# Power_regulator.net
KiCad netlist of a schematic drawn in Altium Designer
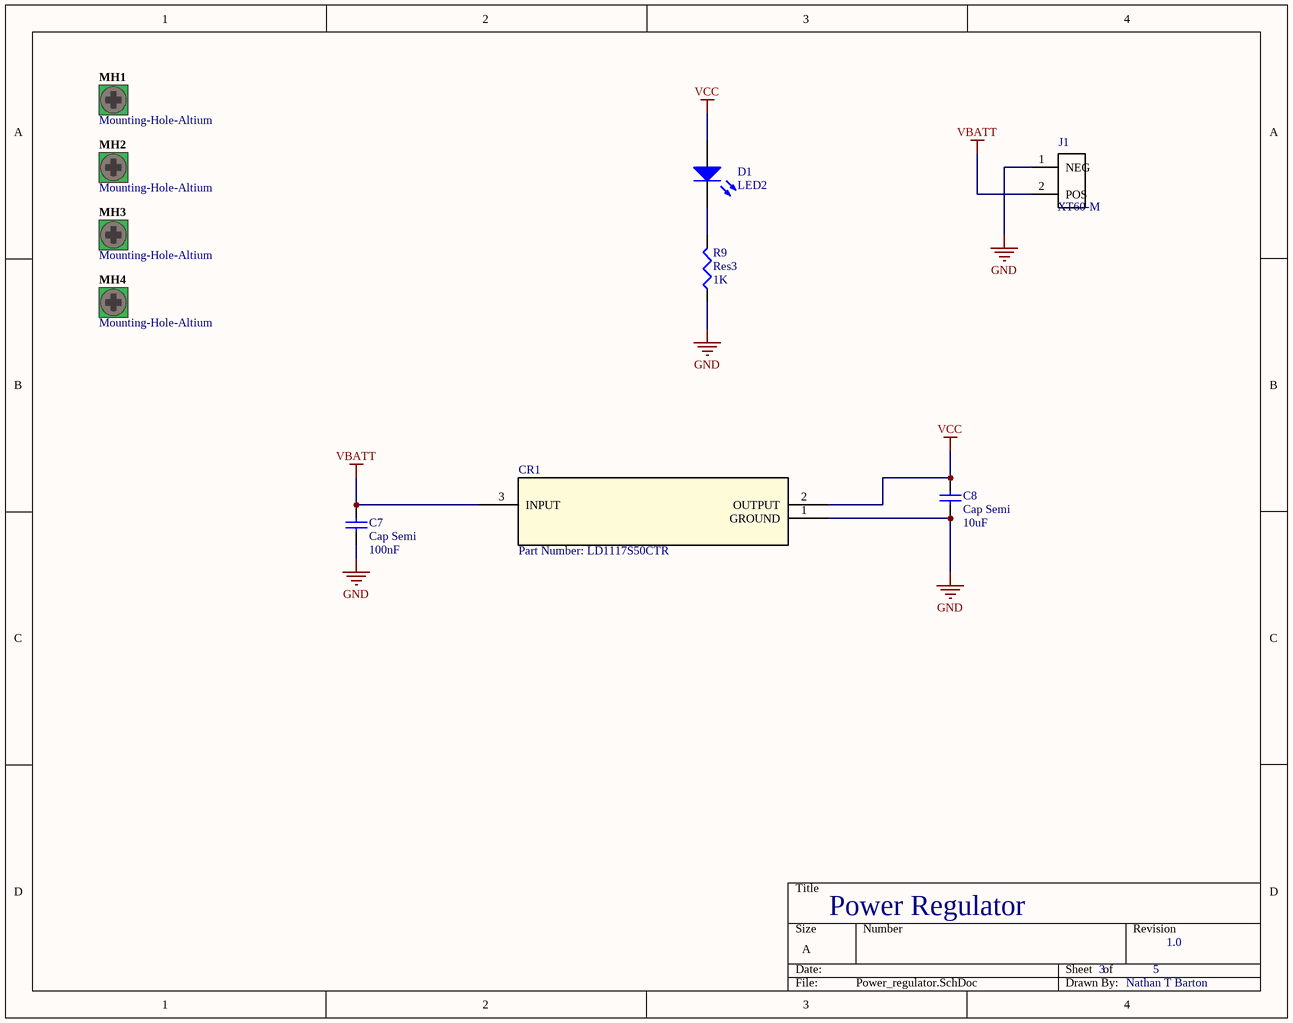
[diagram p0: Power_regulator.SchDoc]

(export (version "E")
  (design (tool "Eeschema 10.0.6"))
  (components
    (comp (ref "C7")
      (value "Cap Semi")
      (footprint "C1206")
      (description "Capacitor (Semiconductor SIM Model)")
      (fields (field (name "ALTIUM_VALUE") "100nF") (field (name "PUBLISHER") "Altium Limited"))
      (libsource (lib "Miscellaneous Devices") (part "Cap Semi"))
    )
    (comp (ref "C8")
      (value "Cap Semi")
      (footprint "C1206")
      (description "Capacitor (Semiconductor SIM Model)")
      (fields (field (name "ALTIUM_VALUE") "10uF") (field (name "PUBLISHER") "Altium Limited"))
      (libsource (lib "Miscellaneous Devices") (part "Cap Semi"))
    )
    (comp (ref "CR1")
      (value "Part Number: LD1117S50CTR")
      (footprint "SOT-223")
      (description "No Description Available")
      (fields
        (field (name "MANUFACTURER_PART_NUMBER") "LD1117S50CTR")
        (field (name "COPYRIGHT") "Copyright (C) 2018 Accelerated Designs. All rights reserved")
      )
      (libsource (lib "spoolbot_library") (part "LD1117S50CTR"))
    )
    (comp (ref "D1")
      (value "LED2")
      (footprint "3.2X1.6X1.1")
      (description "Typical RED, GREEN, YELLOW, AMBER GaAs LED")
      (fields (field (name "PUBLISHER") "Altium Limited"))
      (libsource (lib "Miscellaneous Devices") (part "LED2"))
    )
    (comp (ref "J1")
      (value "XT60-M")
      (footprint "*AMASS_XT60-M")
      (fields (field (name "MF") "AMASS"))
      (libsource (lib "spoolbot_library") (part "XT60-M"))
    )
    (comp (ref "MH1")
      (value "Mounting-Hole-Altium")
      (footprint "Mounting-Hole-Altium")
      (description "Mounting Hole, Altium, 3.8mm pad, 3.4mm plated hole")
      (fields (field (name "PUBLISHER") "Altium"))
      (libsource (lib "Altium Content Vault") (part "Mounting-Hole-Screw"))
    )
    (comp (ref "MH2")
      (value "Mounting-Hole-Altium")
      (footprint "Mounting-Hole-Altium")
      (description "Mounting Hole, Altium, 3.8mm pad, 3.4mm plated hole")
      (fields (field (name "PUBLISHER") "Altium"))
      (libsource (lib "Altium Content Vault") (part "Mounting-Hole-Screw"))
    )
    (comp (ref "MH3")
      (value "Mounting-Hole-Altium")
      (footprint "Mounting-Hole-Altium")
      (description "Mounting Hole, Altium, 3.8mm pad, 3.4mm plated hole")
      (fields (field (name "PUBLISHER") "Altium"))
      (libsource (lib "Altium Content Vault") (part "Mounting-Hole-Screw"))
    )
    (comp (ref "MH4")
      (value "Mounting-Hole-Altium")
      (footprint "Mounting-Hole-Altium")
      (description "Mounting Hole, Altium, 3.8mm pad, 3.4mm plated hole")
      (fields (field (name "PUBLISHER") "Altium"))
      (libsource (lib "Altium Content Vault") (part "Mounting-Hole-Screw"))
    )
    (comp (ref "R9")
      (value "Res3")
      (footprint "J1-0603")
      (description "Resistor")
      (fields (field (name "ALTIUM_VALUE") "1K") (field (name "PUBLISHER") "Altium Limited"))
      (libsource (lib "Miscellaneous Devices") (part "Res3"))
    )
  )
  (nets
    (net (code "1") (name "GND") (class "Default")
      (node (ref "C7") (pin "1") (pinfunction "1_1") (pintype "passive"))
      (node (ref "C8") (pin "1") (pinfunction "1_1") (pintype "passive"))
      (node (ref "CR1") (pin "1") (pinfunction "GROUND_1") (pintype "passive"))
      (node (ref "J1") (pin "1") (pinfunction "NEG_1") (pintype "passive"))
      (node (ref "R9") (pin "1") (pinfunction "1_1") (pintype "passive"))
    )
    (net (code "2") (name "Net-(D1-K)") (class "Default")
      (node (ref "D1") (pin "2") (pinfunction "K_2") (pintype "passive"))
      (node (ref "R9") (pin "2") (pinfunction "2_2") (pintype "passive"))
    )
    (net (code "3") (name "VBATT") (class "Default")
      (node (ref "C7") (pin "2") (pinfunction "2_2") (pintype "passive"))
      (node (ref "CR1") (pin "3") (pinfunction "INPUT_3") (pintype "passive"))
      (node (ref "J1") (pin "2") (pinfunction "POS_2") (pintype "passive"))
    )
    (net (code "4") (name "VCC") (class "Default")
      (node (ref "C8") (pin "2") (pinfunction "2_2") (pintype "passive"))
      (node (ref "CR1") (pin "2") (pinfunction "OUTPUT_2") (pintype "passive"))
      (node (ref "D1") (pin "1") (pinfunction "A_1") (pintype "passive"))
    )
    (net (code "5") (name "unconnected-(MH1-Pad1)") (class "Default")
      (node (ref "MH1") (pin "1") (pinfunction "1_1") (pintype "passive"))
    )
    (net (code "6") (name "unconnected-(MH2-Pad1)") (class "Default")
      (node (ref "MH2") (pin "1") (pinfunction "1_1") (pintype "passive"))
    )
    (net (code "7") (name "unconnected-(MH3-Pad1)") (class "Default")
      (node (ref "MH3") (pin "1") (pinfunction "1_1") (pintype "passive"))
    )
    (net (code "8") (name "unconnected-(MH4-Pad1)") (class "Default")
      (node (ref "MH4") (pin "1") (pinfunction "1_1") (pintype "passive"))
    )
  )
)
